# WagaGSMv3.net
KiCad netlist of a schematic drawn in EAGLE
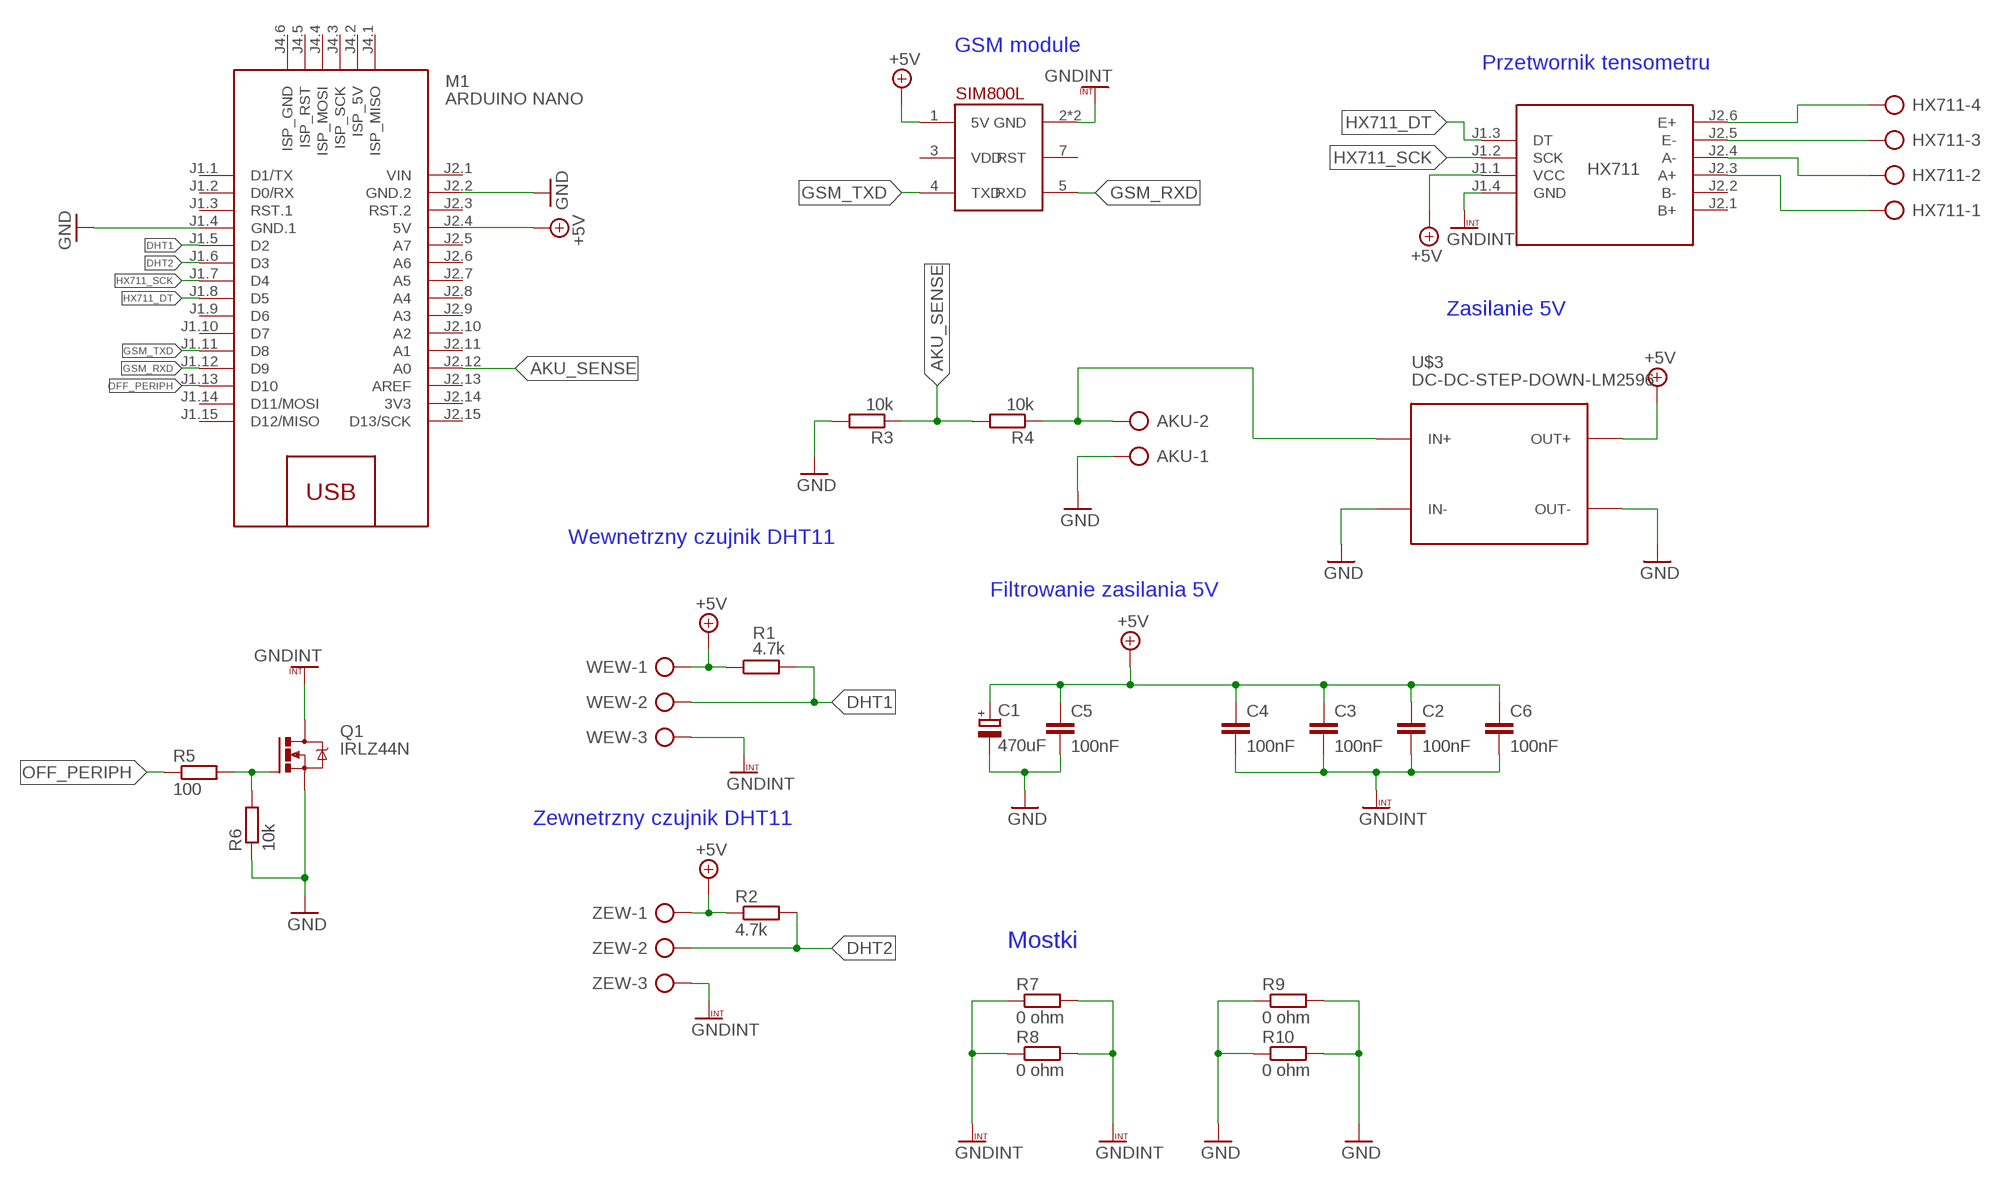
[diagram p0: schematic, sheet 1]

(export (version "E")
  (design (tool "Eeschema 10.0.6"))
  (components
    (comp (ref "AKU")
      (value "AK500/2-H")
      (footprint "eagle-import:AK500_2-H")
      (libsource (lib "eagle-import") (part "AK500/2-H"))
    )
    (comp (ref "C1")
      (value "470uF")
      (footprint "eagle-import:E5-10,5")
      (libsource (lib "eagle-import") (part "CPOL-EUE5-10.5"))
    )
    (comp (ref "C2")
      (value "100nF")
      (footprint "eagle-import:C050-030X075")
      (libsource (lib "eagle-import") (part "C-EU050-030X075"))
    )
    (comp (ref "C3")
      (value "100nF")
      (footprint "eagle-import:C050-030X075")
      (libsource (lib "eagle-import") (part "C-EU050-030X075"))
    )
    (comp (ref "C4")
      (value "100nF")
      (footprint "eagle-import:C050-030X075")
      (libsource (lib "eagle-import") (part "C-EU050-030X075"))
    )
    (comp (ref "C5")
      (value "100nF")
      (footprint "eagle-import:C050-030X075")
      (libsource (lib "eagle-import") (part "C-EU050-030X075"))
    )
    (comp (ref "C6")
      (value "100nF")
      (footprint "eagle-import:C050-030X075")
      (libsource (lib "eagle-import") (part "C-EU050-030X075"))
    )
    (comp (ref "HX711")
      (value "AK300/4")
      (footprint "eagle-import:AK300_4")
      (libsource (lib "eagle-import") (part "AK300/4"))
    )
    (comp (ref "M1")
      (value "ARDUINO NANO")
      (footprint "eagle-import:ARDUINO-NANO-3.0#ISP")
      (libsource (lib "eagle-import") (part "ARDUINO-NANO-3.0#ISP"))
    )
    (comp (ref "Q1")
      (value "IRLZ44N")
      (footprint "eagle-import:TO220BH")
      (libsource (lib "eagle-import") (part "IRFZ48Z"))
    )
    (comp (ref "R1")
      (value "4.7k")
      (footprint "eagle-import:0204_7")
      (libsource (lib "eagle-import") (part "R-EU_0204/7"))
    )
    (comp (ref "R2")
      (value "4.7k")
      (footprint "eagle-import:0204_7")
      (libsource (lib "eagle-import") (part "R-EU_0204/7"))
    )
    (comp (ref "R3")
      (value "10k")
      (footprint "eagle-import:0207_10")
      (libsource (lib "eagle-import") (part "R-EU_0207/10"))
    )
    (comp (ref "R4")
      (value "10k")
      (footprint "eagle-import:0207_10")
      (libsource (lib "eagle-import") (part "R-EU_0207/10"))
    )
    (comp (ref "R5")
      (value "100")
      (footprint "eagle-import:0207_7")
      (libsource (lib "eagle-import") (part "R-EU_0207/7"))
    )
    (comp (ref "R6")
      (value "10k")
      (footprint "eagle-import:0207_7")
      (libsource (lib "eagle-import") (part "R-EU_0207/7"))
    )
    (comp (ref "R7")
      (value "0 ohm")
      (footprint "eagle-import:0204_7")
      (libsource (lib "eagle-import") (part "R-EU_0204/7"))
    )
    (comp (ref "R8")
      (value "0 ohm")
      (footprint "eagle-import:0204_7")
      (libsource (lib "eagle-import") (part "R-EU_0204/7"))
    )
    (comp (ref "R9")
      (value "0 ohm")
      (footprint "eagle-import:0204_7")
      (libsource (lib "eagle-import") (part "R-EU_0204/7"))
    )
    (comp (ref "R10")
      (value "0 ohm")
      (footprint "eagle-import:0204_7")
      (libsource (lib "eagle-import") (part "R-EU_0204/7"))
    )
    (comp (ref "U$1")
      (value "SIM800L")
      (footprint "eagle-import:SIP")
      (libsource (lib "eagle-import") (part "SIM800L"))
    )
    (comp (ref "U$2")
      (value "HX711")
      (footprint "eagle-import:HX711")
      (libsource (lib "eagle-import") (part "HX711"))
    )
    (comp (ref "U$3")
      (value "DC-DC-STEP-DOWN-LM2596")
      (footprint "eagle-import:DC-DC-STEP-DOWN-LM2596")
      (libsource (lib "eagle-import") (part "DC-DC-STEP-DOWN-LM2596"))
    )
    (comp (ref "WEW")
      (value "AK500/3-H")
      (footprint "eagle-import:AK500_3-H")
      (libsource (lib "eagle-import") (part "AK500/3-H"))
    )
    (comp (ref "ZEW")
      (value "AK500/3-H")
      (footprint "eagle-import:AK500_3-H")
      (libsource (lib "eagle-import") (part "AK500/3-H"))
    )
  )
  (nets
    (net (code "1") (name "+5V") (class "Default")
      (node (ref "C1") (pin "+") (pinfunction "+_+") (pintype "passive"))
      (node (ref "C2") (pin "1") (pinfunction "1_1") (pintype "passive"))
      (node (ref "C3") (pin "1") (pinfunction "1_1") (pintype "passive"))
      (node (ref "C4") (pin "1") (pinfunction "1_1") (pintype "passive"))
      (node (ref "C5") (pin "1") (pinfunction "1_1") (pintype "passive"))
      (node (ref "C6") (pin "1") (pinfunction "1_1") (pintype "passive"))
      (node (ref "M1") (pin "J2.4") (pinfunction "5V_J2.4") (pintype "power_in"))
      (node (ref "R1") (pin "1") (pinfunction "1_1") (pintype "passive"))
      (node (ref "R2") (pin "1") (pinfunction "1_1") (pintype "passive"))
      (node (ref "U$1") (pin "1") (pinfunction "5V_1") (pintype "bidirectional"))
      (node (ref "U$2") (pin "J1.1") (pinfunction "VCC_J1.1") (pintype "power_in"))
      (node (ref "U$3") (pin "OUT+") (pinfunction "OUT+_OUT+") (pintype "bidirectional"))
      (node (ref "WEW") (pin "1") (pinfunction "KL_1") (pintype "passive"))
      (node (ref "ZEW") (pin "1") (pinfunction "KL_1") (pintype "passive"))
    )
    (net (code "2") (name "/3V3") (class "Default")
      (node (ref "M1") (pin "J2.14") (pinfunction "3V3_J2.14") (pintype "power_in"))
    )
    (net (code "3") (name "/B-") (class "Default")
      (node (ref "U$2") (pin "J2.2") (pinfunction "B-_J2.2") (pintype "power_in"))
    )
    (net (code "4") (name "/VIN") (class "Default")
      (node (ref "M1") (pin "J2.1") (pinfunction "VIN_J2.1") (pintype "power_in"))
    )
    (net (code "5") (name "AKU_SENSE") (class "Default")
      (node (ref "M1") (pin "J2.12") (pinfunction "A0_J2.12") (pintype "bidirectional"))
      (node (ref "R3") (pin "1") (pinfunction "1_1") (pintype "passive"))
      (node (ref "R4") (pin "2") (pinfunction "2_2") (pintype "passive"))
    )
    (net (code "6") (name "DHT1") (class "Default")
      (node (ref "M1") (pin "J1.5") (pinfunction "D2_J1.5") (pintype "bidirectional"))
      (node (ref "R1") (pin "2") (pinfunction "2_2") (pintype "passive"))
      (node (ref "WEW") (pin "2") (pinfunction "KL_2") (pintype "passive"))
    )
    (net (code "7") (name "DHT2") (class "Default")
      (node (ref "M1") (pin "J1.6") (pinfunction "D3_J1.6") (pintype "bidirectional"))
      (node (ref "R2") (pin "2") (pinfunction "2_2") (pintype "passive"))
      (node (ref "ZEW") (pin "2") (pinfunction "KL_2") (pintype "passive"))
    )
    (net (code "8") (name "GND") (class "Default")
      (node (ref "AKU") (pin "1") (pinfunction "KL_1") (pintype "passive"))
      (node (ref "C1") (pin "-") (pinfunction "-_-") (pintype "passive"))
      (node (ref "C5") (pin "2") (pinfunction "2_2") (pintype "passive"))
      (node (ref "M1") (pin "J1.4") (pinfunction "GND.1_J1.4") (pintype "power_in"))
      (node (ref "M1") (pin "J2.2") (pinfunction "GND.2_J2.2") (pintype "power_in"))
      (node (ref "Q1") (pin "S") (pinfunction "S_S") (pintype "passive"))
      (node (ref "R10") (pin "1") (pinfunction "1_1") (pintype "passive"))
      (node (ref "R10") (pin "2") (pinfunction "2_2") (pintype "passive"))
      (node (ref "R3") (pin "2") (pinfunction "2_2") (pintype "passive"))
      (node (ref "R6") (pin "1") (pinfunction "1_1") (pintype "passive"))
      (node (ref "R9") (pin "1") (pinfunction "1_1") (pintype "passive"))
      (node (ref "R9") (pin "2") (pinfunction "2_2") (pintype "passive"))
      (node (ref "U$3") (pin "IN-") (pinfunction "IN-_IN-") (pintype "bidirectional"))
      (node (ref "U$3") (pin "OUT-") (pinfunction "OUT-_OUT-") (pintype "bidirectional"))
    )
    (net (code "9") (name "GNDINT") (class "Default")
      (node (ref "C2") (pin "2") (pinfunction "2_2") (pintype "passive"))
      (node (ref "C3") (pin "2") (pinfunction "2_2") (pintype "passive"))
      (node (ref "C4") (pin "2") (pinfunction "2_2") (pintype "passive"))
      (node (ref "C6") (pin "2") (pinfunction "2_2") (pintype "passive"))
      (node (ref "Q1") (pin "D") (pinfunction "D_D") (pintype "passive"))
      (node (ref "R7") (pin "1") (pinfunction "1_1") (pintype "passive"))
      (node (ref "R7") (pin "2") (pinfunction "2_2") (pintype "passive"))
      (node (ref "R8") (pin "1") (pinfunction "1_1") (pintype "passive"))
      (node (ref "R8") (pin "2") (pinfunction "2_2") (pintype "passive"))
      (node (ref "U$1") (pin "2") (pinfunction "GND_2") (pintype "bidirectional"))
      (node (ref "U$1") (pin "6") (pinfunction "GND_6") (pintype "bidirectional"))
      (node (ref "U$2") (pin "J1.4") (pinfunction "GND_J1.4") (pintype "power_in"))
      (node (ref "WEW") (pin "3") (pinfunction "KL_3") (pintype "passive"))
      (node (ref "ZEW") (pin "3") (pinfunction "KL_3") (pintype "passive"))
    )
    (net (code "10") (name "GSM_RXD") (class "Default")
      (node (ref "M1") (pin "J1.12") (pinfunction "D9_J1.12") (pintype "bidirectional"))
      (node (ref "U$1") (pin "5") (pinfunction "RXD_5") (pintype "bidirectional"))
    )
    (net (code "11") (name "GSM_TXD") (class "Default")
      (node (ref "M1") (pin "J1.11") (pinfunction "D8_J1.11") (pintype "bidirectional"))
      (node (ref "U$1") (pin "4") (pinfunction "TXD_4") (pintype "bidirectional"))
    )
    (net (code "12") (name "HX711_DT") (class "Default")
      (node (ref "M1") (pin "J1.8") (pinfunction "D5_J1.8") (pintype "bidirectional"))
      (node (ref "U$2") (pin "J1.3") (pinfunction "DT_J1.3") (pintype "bidirectional"))
    )
    (net (code "13") (name "HX711_SCK") (class "Default")
      (node (ref "M1") (pin "J1.7") (pinfunction "D4_J1.7") (pintype "bidirectional"))
      (node (ref "U$2") (pin "J1.2") (pinfunction "SCK_J1.2") (pintype "bidirectional"))
    )
    (net (code "14") (name "Net-(AKUB-KL)") (class "Default")
      (node (ref "AKU") (pin "2") (pinfunction "KL_2") (pintype "passive"))
      (node (ref "R4") (pin "1") (pinfunction "1_1") (pintype "passive"))
      (node (ref "U$3") (pin "IN+") (pinfunction "IN+_IN+") (pintype "bidirectional"))
    )
    (net (code "15") (name "Net-(HX711A-KL)") (class "Default")
      (node (ref "HX711") (pin "1") (pinfunction "KL_1") (pintype "passive"))
      (node (ref "U$2") (pin "J2.3") (pinfunction "A+_J2.3") (pintype "power_in"))
    )
    (net (code "16") (name "Net-(HX711B-KL)") (class "Default")
      (node (ref "HX711") (pin "2") (pinfunction "KL_2") (pintype "passive"))
      (node (ref "U$2") (pin "J2.4") (pinfunction "A-_J2.4") (pintype "bidirectional"))
    )
    (net (code "17") (name "Net-(HX711C-KL)") (class "Default")
      (node (ref "HX711") (pin "3") (pinfunction "KL_3") (pintype "passive"))
      (node (ref "U$2") (pin "J2.5") (pinfunction "E-_J2.5") (pintype "bidirectional"))
    )
    (net (code "18") (name "Net-(HX711D-KL)") (class "Default")
      (node (ref "HX711") (pin "4") (pinfunction "KL_4") (pintype "passive"))
      (node (ref "U$2") (pin "J2.6") (pinfunction "E+_J2.6") (pintype "bidirectional"))
    )
    (net (code "19") (name "Net-(Q1-PadG)") (class "Default")
      (node (ref "Q1") (pin "G") (pinfunction "G_G") (pintype "passive"))
      (node (ref "R5") (pin "2") (pinfunction "2_2") (pintype "passive"))
      (node (ref "R6") (pin "2") (pinfunction "2_2") (pintype "passive"))
    )
    (net (code "20") (name "OFF_PERIPH") (class "Default")
      (node (ref "M1") (pin "J1.13") (pinfunction "D10_J1.13") (pintype "bidirectional"))
      (node (ref "R5") (pin "1") (pinfunction "1_1") (pintype "passive"))
    )
    (net (code "21") (name "unconnected-(M1-A1-PadJ2.11)") (class "Default")
      (node (ref "M1") (pin "J2.11") (pinfunction "A1_J2.11") (pintype "bidirectional"))
    )
    (net (code "22") (name "unconnected-(M1-A2-PadJ2.10)") (class "Default")
      (node (ref "M1") (pin "J2.10") (pinfunction "A2_J2.10") (pintype "bidirectional"))
    )
    (net (code "23") (name "unconnected-(M1-A3-PadJ2.9)") (class "Default")
      (node (ref "M1") (pin "J2.9") (pinfunction "A3_J2.9") (pintype "bidirectional"))
    )
    (net (code "24") (name "unconnected-(M1-A4-PadJ2.8)") (class "Default")
      (node (ref "M1") (pin "J2.8") (pinfunction "A4_J2.8") (pintype "bidirectional"))
    )
    (net (code "25") (name "unconnected-(M1-A5-PadJ2.7)") (class "Default")
      (node (ref "M1") (pin "J2.7") (pinfunction "A5_J2.7") (pintype "bidirectional"))
    )
    (net (code "26") (name "unconnected-(M1-A6-PadJ2.6)") (class "Default")
      (node (ref "M1") (pin "J2.6") (pinfunction "A6_J2.6") (pintype "bidirectional"))
    )
    (net (code "27") (name "unconnected-(M1-A7-PadJ2.5)") (class "Default")
      (node (ref "M1") (pin "J2.5") (pinfunction "A7_J2.5") (pintype "bidirectional"))
    )
    (net (code "28") (name "unconnected-(M1-AREF-PadJ2.13)") (class "Default")
      (node (ref "M1") (pin "J2.13") (pinfunction "AREF_J2.13") (pintype "bidirectional"))
    )
    (net (code "29") (name "unconnected-(M1-D0{slash}RX-PadJ1.2)") (class "Default")
      (node (ref "M1") (pin "J1.2") (pinfunction "D0/RX_J1.2") (pintype "bidirectional"))
    )
    (net (code "30") (name "unconnected-(M1-D1{slash}TX-PadJ1.1)") (class "Default")
      (node (ref "M1") (pin "J1.1") (pinfunction "D1/TX_J1.1") (pintype "bidirectional"))
    )
    (net (code "31") (name "unconnected-(M1-D6-PadJ1.9)") (class "Default")
      (node (ref "M1") (pin "J1.9") (pinfunction "D6_J1.9") (pintype "bidirectional"))
    )
    (net (code "32") (name "unconnected-(M1-D7-PadJ1.10)") (class "Default")
      (node (ref "M1") (pin "J1.10") (pinfunction "D7_J1.10") (pintype "bidirectional"))
    )
    (net (code "33") (name "unconnected-(M1-D11{slash}MOSI-PadJ1.14)") (class "Default")
      (node (ref "M1") (pin "J1.14") (pinfunction "D11/MOSI_J1.14") (pintype "bidirectional"))
    )
    (net (code "34") (name "unconnected-(M1-D12{slash}MISO-PadJ1.15)") (class "Default")
      (node (ref "M1") (pin "J1.15") (pinfunction "D12/MISO_J1.15") (pintype "bidirectional"))
    )
    (net (code "35") (name "unconnected-(M1-D13{slash}SCK-PadJ2.15)") (class "Default")
      (node (ref "M1") (pin "J2.15") (pinfunction "D13/SCK_J2.15") (pintype "bidirectional"))
    )
    (net (code "36") (name "unconnected-(M1-ISP_5V-PadJ4.2)") (class "Default")
      (node (ref "M1") (pin "J4.2") (pinfunction "ISP_5V_J4.2") (pintype "bidirectional"))
    )
    (net (code "37") (name "unconnected-(M1-ISP_GND-PadJ4.6)") (class "Default")
      (node (ref "M1") (pin "J4.6") (pinfunction "ISP_GND_J4.6") (pintype "bidirectional"))
    )
    (net (code "38") (name "unconnected-(M1-ISP_MISO-PadJ4.1)") (class "Default")
      (node (ref "M1") (pin "J4.1") (pinfunction "ISP_MISO_J4.1") (pintype "bidirectional"))
    )
    (net (code "39") (name "unconnected-(M1-ISP_MOSI-PadJ4.4)") (class "Default")
      (node (ref "M1") (pin "J4.4") (pinfunction "ISP_MOSI_J4.4") (pintype "bidirectional"))
    )
    (net (code "40") (name "unconnected-(M1-ISP_RST-PadJ4.5)") (class "Default")
      (node (ref "M1") (pin "J4.5") (pinfunction "ISP_RST_J4.5") (pintype "bidirectional"))
    )
    (net (code "41") (name "unconnected-(M1-ISP_SCK-PadJ4.3)") (class "Default")
      (node (ref "M1") (pin "J4.3") (pinfunction "ISP_SCK_J4.3") (pintype "bidirectional"))
    )
    (net (code "42") (name "unconnected-(M1-RST.1-PadJ1.3)") (class "Default")
      (node (ref "M1") (pin "J1.3") (pinfunction "RST.1_J1.3") (pintype "bidirectional"))
    )
    (net (code "43") (name "unconnected-(M1-RST.2-PadJ2.3)") (class "Default")
      (node (ref "M1") (pin "J2.3") (pinfunction "RST.2_J2.3") (pintype "bidirectional"))
    )
    (net (code "44") (name "unconnected-(U$1-RST-Pad7)") (class "Default")
      (node (ref "U$1") (pin "7") (pinfunction "RST_7") (pintype "bidirectional"))
    )
    (net (code "45") (name "unconnected-(U$1-VDD-Pad3)") (class "Default")
      (node (ref "U$1") (pin "3") (pinfunction "VDD_3") (pintype "bidirectional"))
    )
    (net (code "46") (name "unconnected-(U$2-B+-PadJ2.1)") (class "Default")
      (node (ref "U$2") (pin "J2.1") (pinfunction "B+_J2.1") (pintype "bidirectional"))
    )
  )
)
